# Un_Battery.net
KiCad netlist of a schematic drawn in EAGLE
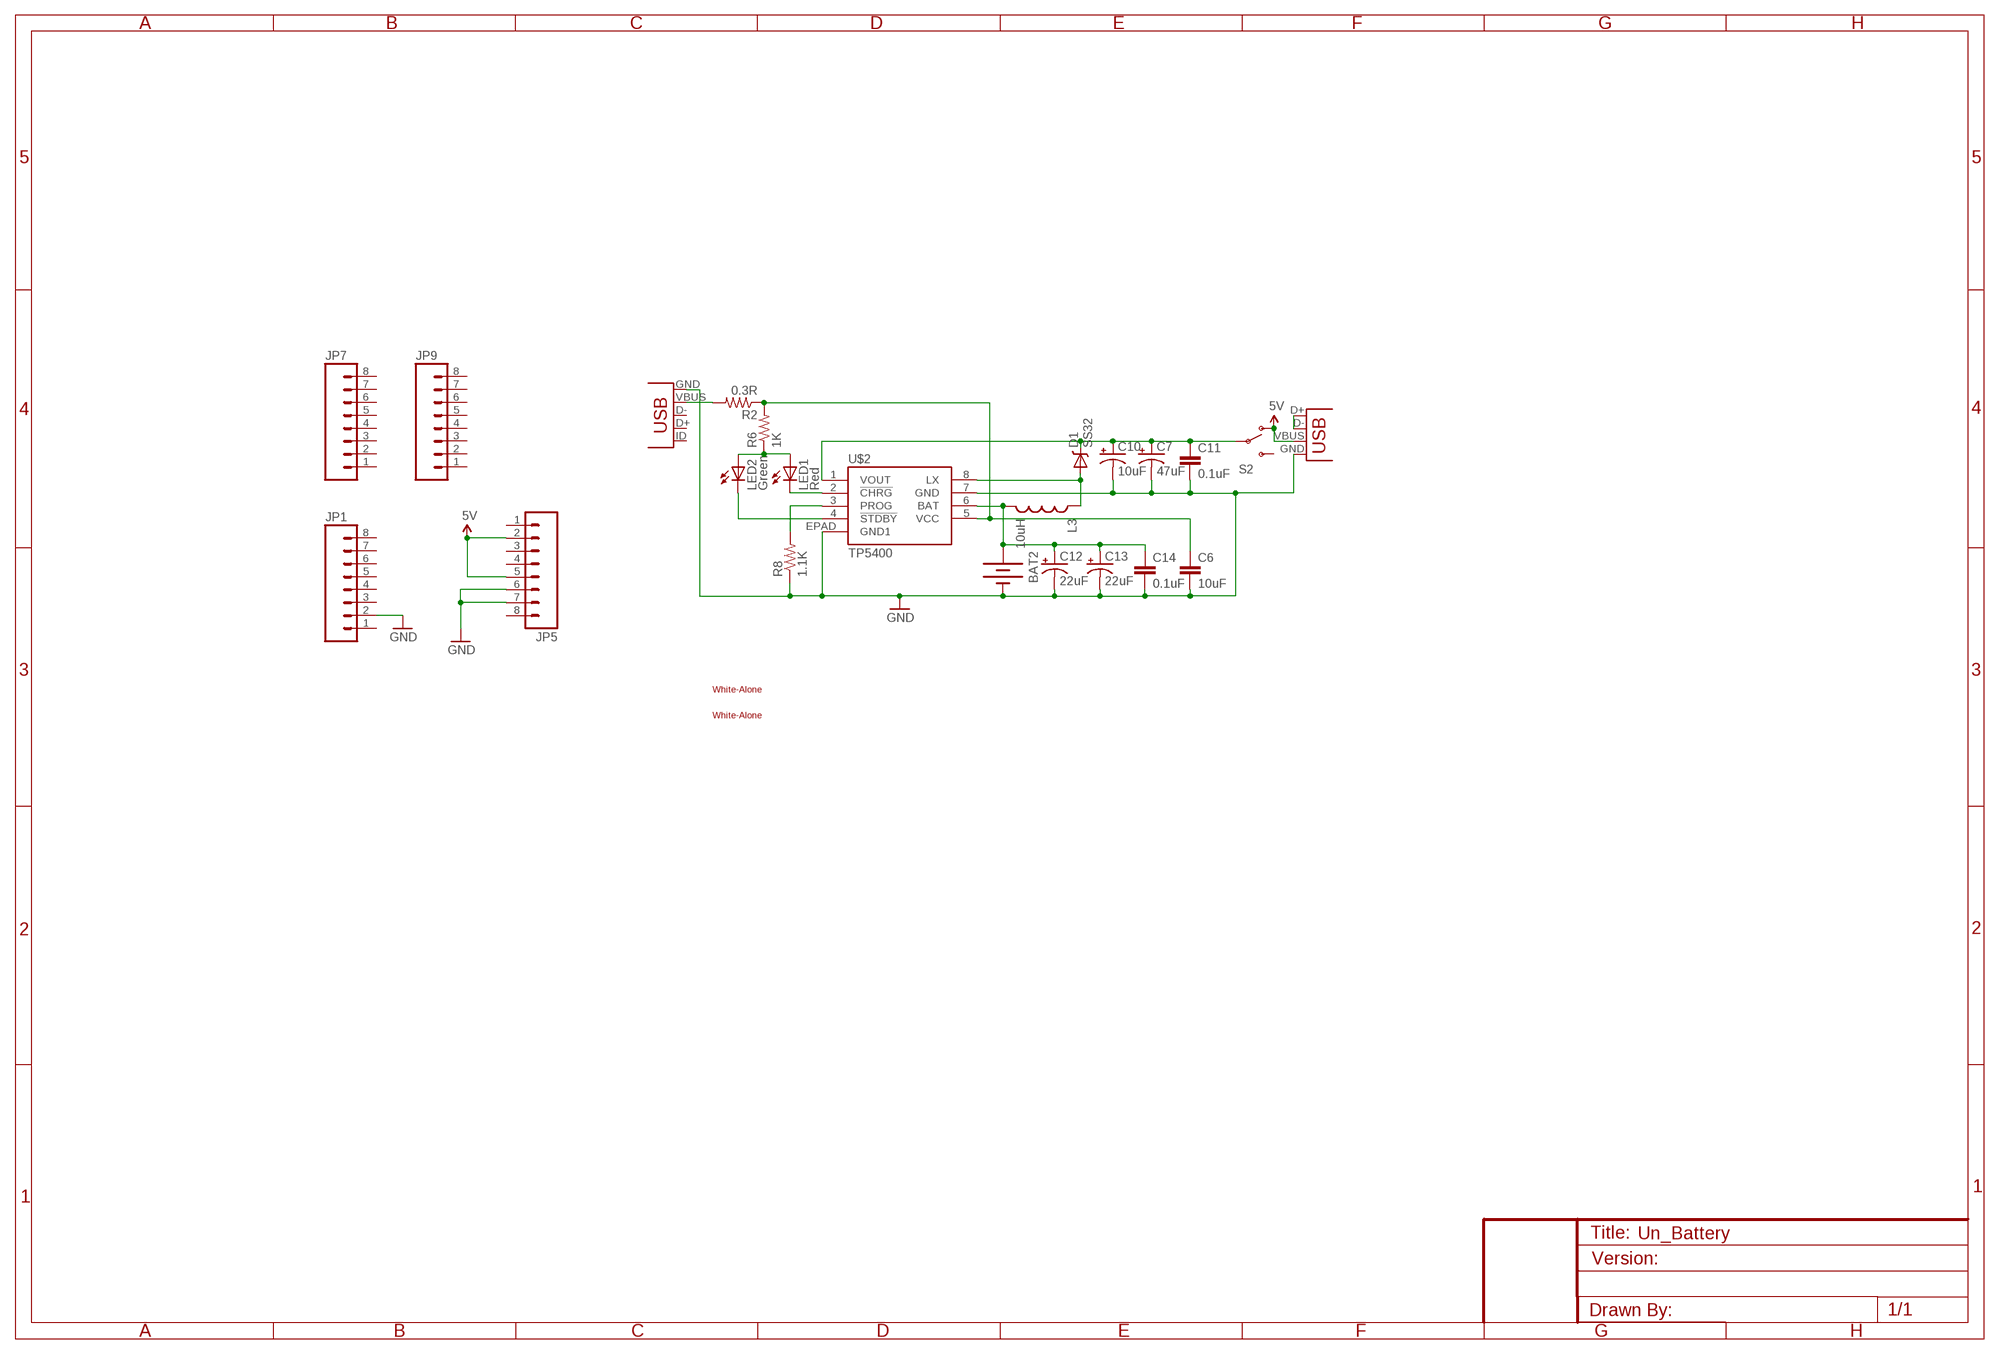
[diagram p0: schematic, sheet 1]

(export (version "E")
  (design (tool "Eeschema 10.0.6"))
  (components
    (comp (ref "BAT2")
      (value "BATTERYLIPO")
      (footprint "eagle-import:BATTERY-LIPO")
      (libsource (lib "eagle-import") (part "BATTERYLIPO"))
    )
    (comp (ref "C6")
      (value "10uF")
      (footprint "eagle-import:1206")
      (libsource (lib "eagle-import") (part "CAP1206"))
    )
    (comp (ref "C7")
      (value "47uF")
      (footprint "eagle-import:PANASONIC_D")
      (libsource (lib "eagle-import") (part "CAP_POLD"))
    )
    (comp (ref "C10")
      (value "10uF")
      (footprint "eagle-import:EIA3216")
      (libsource (lib "eagle-import") (part "CAP_POL1206"))
    )
    (comp (ref "C11")
      (value "0.1uF")
      (footprint "eagle-import:1206")
      (libsource (lib "eagle-import") (part "CAP1206"))
    )
    (comp (ref "C12")
      (value "22uF")
      (footprint "eagle-import:EIA3216")
      (libsource (lib "eagle-import") (part "CAP_POL1206"))
    )
    (comp (ref "C13")
      (value "22uF")
      (footprint "eagle-import:EIA3216")
      (libsource (lib "eagle-import") (part "CAP_POL1206"))
    )
    (comp (ref "C14")
      (value "0.1uF")
      (footprint "eagle-import:1206")
      (libsource (lib "eagle-import") (part "CAP1206"))
    )
    (comp (ref "D1")
      (value "SS32")
      (footprint "eagle-import:SMA-DIODE")
      (libsource (lib "eagle-import") (part "DIODE-SCHOTTKY_"))
    )
    (comp (ref "JP1")
      (value "M081X08")
      (footprint "eagle-import:1X08")
      (libsource (lib "eagle-import") (part "M081X08"))
    )
    (comp (ref "JP5")
      (value "M081X08")
      (footprint "eagle-import:1X08")
      (libsource (lib "eagle-import") (part "M081X08"))
    )
    (comp (ref "JP7")
      (value "M081X08")
      (footprint "eagle-import:1X08")
      (libsource (lib "eagle-import") (part "M081X08"))
    )
    (comp (ref "JP9")
      (value "M081X08")
      (footprint "eagle-import:1X08")
      (libsource (lib "eagle-import") (part "M081X08"))
    )
    (comp (ref "L3")
      (value "10uH")
      (footprint "eagle-import:CR75")
      (libsource (lib "eagle-import") (part "INDUCTORCR75"))
    )
    (comp (ref "LED1")
      (value "Red")
      (footprint "eagle-import:LED-0805")
      (libsource (lib "eagle-import") (part "LED0805"))
    )
    (comp (ref "LED2")
      (value "Green")
      (footprint "eagle-import:LED-0805")
      (libsource (lib "eagle-import") (part "LED0805"))
    )
    (comp (ref "R2")
      (value "0.3R")
      (footprint "eagle-import:1206")
      (libsource (lib "eagle-import") (part "RESISTOR1206"))
    )
    (comp (ref "R6")
      (value "1K")
      (footprint "eagle-import:0805")
      (libsource (lib "eagle-import") (part "RESISTOR0805-RES"))
    )
    (comp (ref "R8")
      (value "1.1K")
      (footprint "eagle-import:0805")
      (libsource (lib "eagle-import") (part "RESISTOR0805-RES"))
    )
    (comp (ref "S2")
      (value "SWITCH-SPST")
      (footprint "eagle-import:SWITCH-SPDT2")
      (libsource (lib "eagle-import") (part "SWITCH-SPST"))
    )
    (comp (ref "U$2")
      (value "TP5400")
      (footprint "eagle-import:SO08-EPAD")
      (libsource (lib "eagle-import") (part "TP5400"))
    )
    (comp (ref "U$4")
      (value "WHITE-ALONE_2")
      (footprint "eagle-import:WHITE-ALONE_2")
      (libsource (lib "eagle-import") (part "WHITE-ALONE_2"))
    )
    (comp (ref "U$5")
      (value "WHITE-ALONE_2")
      (footprint "eagle-import:WHITE-ALONE_2")
      (libsource (lib "eagle-import") (part "WHITE-ALONE_2"))
    )
    (comp (ref "U$6")
      (value "USB_5-SMD")
      (footprint "eagle-import:USB-MINIB")
      (libsource (lib "eagle-import") (part "USB_5-SMD"))
    )
    (comp (ref "X2")
      (value "USB-A-S")
      (footprint "eagle-import:USB-A-S")
      (libsource (lib "eagle-import") (part "USB-A-S"))
    )
  )
  (nets
    (net (code "1") (name "5V") (class "Default")
      (node (ref "JP5") (pin "2") (pinfunction "2_2") (pintype "passive"))
      (node (ref "JP5") (pin "5") (pinfunction "5_5") (pintype "passive"))
      (node (ref "S2") (pin "1") (pinfunction "O_1") (pintype "passive"))
      (node (ref "X2") (pin "VBUS") (pinfunction "VBUS_VBUS") (pintype "bidirectional"))
    )
    (net (code "2") (name "GND") (class "Default")
      (node (ref "BAT2") (pin "-") (pinfunction "-_-") (pintype "power_in"))
      (node (ref "C10") (pin "C") (pinfunction "-_C") (pintype "passive"))
      (node (ref "C11") (pin "2") (pinfunction "2_2") (pintype "passive"))
      (node (ref "C12") (pin "C") (pinfunction "-_C") (pintype "passive"))
      (node (ref "C13") (pin "C") (pinfunction "-_C") (pintype "passive"))
      (node (ref "C14") (pin "2") (pinfunction "2_2") (pintype "passive"))
      (node (ref "C6") (pin "2") (pinfunction "2_2") (pintype "passive"))
      (node (ref "C7") (pin "-") (pinfunction "-_-") (pintype "passive"))
      (node (ref "JP1") (pin "2") (pinfunction "2_2") (pintype "passive"))
      (node (ref "JP5") (pin "6") (pinfunction "6_6") (pintype "passive"))
      (node (ref "JP5") (pin "7") (pinfunction "7_7") (pintype "passive"))
      (node (ref "R8") (pin "1") (pinfunction "1_1") (pintype "passive"))
      (node (ref "U$2") (pin "7") (pinfunction "GND_7") (pintype "bidirectional"))
      (node (ref "U$2") (pin "EPAD") (pinfunction "GND1_EPAD") (pintype "power_in"))
      (node (ref "U$6") (pin "GND") (pinfunction "GND_GND") (pintype "bidirectional"))
      (node (ref "X2") (pin "GND") (pinfunction "GND_GND") (pintype "bidirectional"))
    )
    (net (code "3") (name "Net-(C10-+)") (class "Default")
      (node (ref "C10") (pin "A") (pinfunction "+_A") (pintype "passive"))
      (node (ref "C11") (pin "1") (pinfunction "1_1") (pintype "passive"))
      (node (ref "C7") (pin "+") (pinfunction "+_+") (pintype "passive"))
      (node (ref "D1") (pin "C") (pinfunction "C_C") (pintype "passive"))
      (node (ref "S2") (pin "2") (pinfunction "P_2") (pintype "passive"))
      (node (ref "U$2") (pin "1") (pinfunction "VOUT_1") (pintype "bidirectional"))
    )
    (net (code "4") (name "Net-(C12-+)") (class "Default")
      (node (ref "BAT2") (pin "+") (pinfunction "+_+") (pintype "power_in"))
      (node (ref "C12") (pin "A") (pinfunction "+_A") (pintype "passive"))
      (node (ref "C13") (pin "A") (pinfunction "+_A") (pintype "passive"))
      (node (ref "C14") (pin "1") (pinfunction "1_1") (pintype "passive"))
      (node (ref "L3") (pin "P$2") (pinfunction "2_P$2") (pintype "passive"))
      (node (ref "U$2") (pin "6") (pinfunction "BAT_6") (pintype "bidirectional"))
    )
    (net (code "5") (name "Net-(L3-1)") (class "Default")
      (node (ref "D1") (pin "A") (pinfunction "A_A") (pintype "passive"))
      (node (ref "L3") (pin "P$1") (pinfunction "1_P$1") (pintype "passive"))
      (node (ref "U$2") (pin "8") (pinfunction "LX_8") (pintype "power_in"))
    )
    (net (code "6") (name "Net-(LED1-A)") (class "Default")
      (node (ref "LED1") (pin "1") (pinfunction "A_1") (pintype "passive"))
      (node (ref "LED2") (pin "1") (pinfunction "A_1") (pintype "passive"))
      (node (ref "R6") (pin "1") (pinfunction "1_1") (pintype "passive"))
    )
    (net (code "7") (name "Net-(LED1-C)") (class "Default")
      (node (ref "LED1") (pin "2") (pinfunction "C_2") (pintype "passive"))
      (node (ref "U$2") (pin "2") (pinfunction "~{CHRG}_2") (pintype "bidirectional"))
    )
    (net (code "8") (name "Net-(LED2-C)") (class "Default")
      (node (ref "LED2") (pin "2") (pinfunction "C_2") (pintype "passive"))
      (node (ref "U$2") (pin "4") (pinfunction "~{STDBY}_4") (pintype "power_in"))
    )
    (net (code "9") (name "Net-(R2-Pad2)") (class "Default")
      (node (ref "R2") (pin "2") (pinfunction "2_2") (pintype "passive"))
      (node (ref "U$6") (pin "VBUS") (pinfunction "VBUS_VBUS") (pintype "bidirectional"))
    )
    (net (code "10") (name "Net-(U$2-PROG)") (class "Default")
      (node (ref "R8") (pin "2") (pinfunction "2_2") (pintype "passive"))
      (node (ref "U$2") (pin "3") (pinfunction "PROG_3") (pintype "bidirectional"))
    )
    (net (code "11") (name "Net-(U$2-VCC)") (class "Default")
      (node (ref "C6") (pin "1") (pinfunction "1_1") (pintype "passive"))
      (node (ref "R2") (pin "1") (pinfunction "1_1") (pintype "passive"))
      (node (ref "R6") (pin "2") (pinfunction "2_2") (pintype "passive"))
      (node (ref "U$2") (pin "5") (pinfunction "VCC_5") (pintype "bidirectional"))
    )
    (net (code "12") (name "Net-(X2-PadD+)") (class "Default")
      (node (ref "X2") (pin "D+") (pinfunction "D+_D+") (pintype "bidirectional"))
      (node (ref "X2") (pin "D-") (pinfunction "D-_D-") (pintype "bidirectional"))
    )
    (net (code "13") (name "unconnected-(JP1-Pad1)") (class "Default")
      (node (ref "JP1") (pin "1") (pinfunction "1_1") (pintype "passive"))
    )
    (net (code "14") (name "unconnected-(JP1-Pad3)") (class "Default")
      (node (ref "JP1") (pin "3") (pinfunction "3_3") (pintype "passive"))
    )
    (net (code "15") (name "unconnected-(JP1-Pad4)") (class "Default")
      (node (ref "JP1") (pin "4") (pinfunction "4_4") (pintype "passive"))
    )
    (net (code "16") (name "unconnected-(JP1-Pad5)") (class "Default")
      (node (ref "JP1") (pin "5") (pinfunction "5_5") (pintype "passive"))
    )
    (net (code "17") (name "unconnected-(JP1-Pad6)") (class "Default")
      (node (ref "JP1") (pin "6") (pinfunction "6_6") (pintype "passive"))
    )
    (net (code "18") (name "unconnected-(JP1-Pad7)") (class "Default")
      (node (ref "JP1") (pin "7") (pinfunction "7_7") (pintype "passive"))
    )
    (net (code "19") (name "unconnected-(JP1-Pad8)") (class "Default")
      (node (ref "JP1") (pin "8") (pinfunction "8_8") (pintype "passive"))
    )
    (net (code "20") (name "unconnected-(JP5-Pad1)") (class "Default")
      (node (ref "JP5") (pin "1") (pinfunction "1_1") (pintype "passive"))
    )
    (net (code "21") (name "unconnected-(JP5-Pad3)") (class "Default")
      (node (ref "JP5") (pin "3") (pinfunction "3_3") (pintype "passive"))
    )
    (net (code "22") (name "unconnected-(JP5-Pad4)") (class "Default")
      (node (ref "JP5") (pin "4") (pinfunction "4_4") (pintype "passive"))
    )
    (net (code "23") (name "unconnected-(JP5-Pad8)") (class "Default")
      (node (ref "JP5") (pin "8") (pinfunction "8_8") (pintype "passive"))
    )
    (net (code "24") (name "unconnected-(JP7-Pad1)") (class "Default")
      (node (ref "JP7") (pin "1") (pinfunction "1_1") (pintype "passive"))
    )
    (net (code "25") (name "unconnected-(JP7-Pad2)") (class "Default")
      (node (ref "JP7") (pin "2") (pinfunction "2_2") (pintype "passive"))
    )
    (net (code "26") (name "unconnected-(JP7-Pad3)") (class "Default")
      (node (ref "JP7") (pin "3") (pinfunction "3_3") (pintype "passive"))
    )
    (net (code "27") (name "unconnected-(JP7-Pad4)") (class "Default")
      (node (ref "JP7") (pin "4") (pinfunction "4_4") (pintype "passive"))
    )
    (net (code "28") (name "unconnected-(JP7-Pad5)") (class "Default")
      (node (ref "JP7") (pin "5") (pinfunction "5_5") (pintype "passive"))
    )
    (net (code "29") (name "unconnected-(JP7-Pad6)") (class "Default")
      (node (ref "JP7") (pin "6") (pinfunction "6_6") (pintype "passive"))
    )
    (net (code "30") (name "unconnected-(JP7-Pad7)") (class "Default")
      (node (ref "JP7") (pin "7") (pinfunction "7_7") (pintype "passive"))
    )
    (net (code "31") (name "unconnected-(JP7-Pad8)") (class "Default")
      (node (ref "JP7") (pin "8") (pinfunction "8_8") (pintype "passive"))
    )
    (net (code "32") (name "unconnected-(JP9-Pad1)") (class "Default")
      (node (ref "JP9") (pin "1") (pinfunction "1_1") (pintype "passive"))
    )
    (net (code "33") (name "unconnected-(JP9-Pad2)") (class "Default")
      (node (ref "JP9") (pin "2") (pinfunction "2_2") (pintype "passive"))
    )
    (net (code "34") (name "unconnected-(JP9-Pad3)") (class "Default")
      (node (ref "JP9") (pin "3") (pinfunction "3_3") (pintype "passive"))
    )
    (net (code "35") (name "unconnected-(JP9-Pad4)") (class "Default")
      (node (ref "JP9") (pin "4") (pinfunction "4_4") (pintype "passive"))
    )
    (net (code "36") (name "unconnected-(JP9-Pad5)") (class "Default")
      (node (ref "JP9") (pin "5") (pinfunction "5_5") (pintype "passive"))
    )
    (net (code "37") (name "unconnected-(JP9-Pad6)") (class "Default")
      (node (ref "JP9") (pin "6") (pinfunction "6_6") (pintype "passive"))
    )
    (net (code "38") (name "unconnected-(JP9-Pad7)") (class "Default")
      (node (ref "JP9") (pin "7") (pinfunction "7_7") (pintype "passive"))
    )
    (net (code "39") (name "unconnected-(JP9-Pad8)") (class "Default")
      (node (ref "JP9") (pin "8") (pinfunction "8_8") (pintype "passive"))
    )
    (net (code "40") (name "unconnected-(S2-S-Pad3)") (class "Default")
      (node (ref "S2") (pin "3") (pinfunction "S_3") (pintype "passive"))
    )
    (net (code "41") (name "unconnected-(U$6-PadD+)") (class "Default")
      (node (ref "U$6") (pin "D+") (pinfunction "D+_D+") (pintype "bidirectional"))
    )
    (net (code "42") (name "unconnected-(U$6-PadD-)") (class "Default")
      (node (ref "U$6") (pin "D-") (pinfunction "D-_D-") (pintype "bidirectional"))
    )
    (net (code "43") (name "unconnected-(U$6-USBID-PadID)") (class "Default")
      (node (ref "U$6") (pin "ID") (pinfunction "USBID_ID") (pintype "bidirectional"))
    )
  )
)
